# rgb_3R.net
KiCad netlist of a schematic drawn in EAGLE
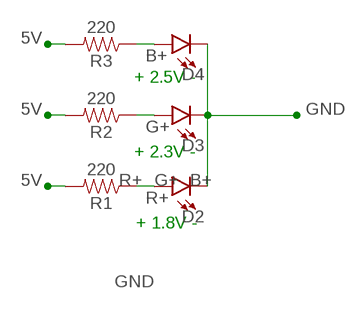
[diagram p0: schematic, sheet 1]

(export (version "E")
  (design (tool "Eeschema 10.0.6"))
  (components
    (comp (ref "D2")
      (value "LED-3MM-NO_SILK")
      (footprint "eagle-import:LED_3MM-NS")
      (libsource (lib "eagle-import") (part "LED-3MM-NO_SILK"))
    )
    (comp (ref "D3")
      (value "LED-3MM-NO_SILK")
      (footprint "eagle-import:LED_3MM-NS")
      (libsource (lib "eagle-import") (part "LED-3MM-NO_SILK"))
    )
    (comp (ref "D4")
      (value "LED-3MM-NO_SILK")
      (footprint "eagle-import:LED_3MM-NS")
      (libsource (lib "eagle-import") (part "LED-3MM-NO_SILK"))
    )
    (comp (ref "R1")
      (value "220")
      (footprint "eagle-import:0603")
      (libsource (lib "eagle-import") (part "220OHM-0603-1/10W-1%"))
    )
    (comp (ref "R2")
      (value "220")
      (footprint "eagle-import:0603")
      (libsource (lib "eagle-import") (part "220OHM-0603-1/10W-1%"))
    )
    (comp (ref "R3")
      (value "220")
      (footprint "eagle-import:0603")
      (libsource (lib "eagle-import") (part "220OHM-0603-1/10W-1%"))
    )
  )
  (nets
    (net (code "1") (name "/5V") (class "Default")
      (node (ref "R3") (pin "2") (pinfunction "2_2") (pintype "passive"))
    )
    (net (code "2") (name "/B+") (class "Default")
      (node (ref "D4") (pin "A") (pinfunction "A_A") (pintype "passive"))
      (node (ref "R3") (pin "1") (pinfunction "1_1") (pintype "passive"))
    )
    (net (code "3") (name "/G+") (class "Default")
      (node (ref "D3") (pin "A") (pinfunction "A_A") (pintype "passive"))
      (node (ref "R2") (pin "1") (pinfunction "1_1") (pintype "passive"))
    )
    (net (code "4") (name "/GND") (class "Default")
      (node (ref "D2") (pin "K") (pinfunction "C_K") (pintype "passive"))
      (node (ref "D3") (pin "K") (pinfunction "C_K") (pintype "passive"))
      (node (ref "D4") (pin "K") (pinfunction "C_K") (pintype "passive"))
    )
    (net (code "5") (name "/R+") (class "Default")
      (node (ref "D2") (pin "A") (pinfunction "A_A") (pintype "passive"))
      (node (ref "R1") (pin "1") (pinfunction "1_1") (pintype "passive"))
    )
    (net (code "6") (name "unconnected-(R1-Pad2)") (class "Default")
      (node (ref "R1") (pin "2") (pinfunction "2_2") (pintype "passive"))
    )
    (net (code "7") (name "unconnected-(R2-Pad2)") (class "Default")
      (node (ref "R2") (pin "2") (pinfunction "2_2") (pintype "passive"))
    )
  )
)
